# PIC.net
KiCad netlist of a schematic drawn in Altium Designer
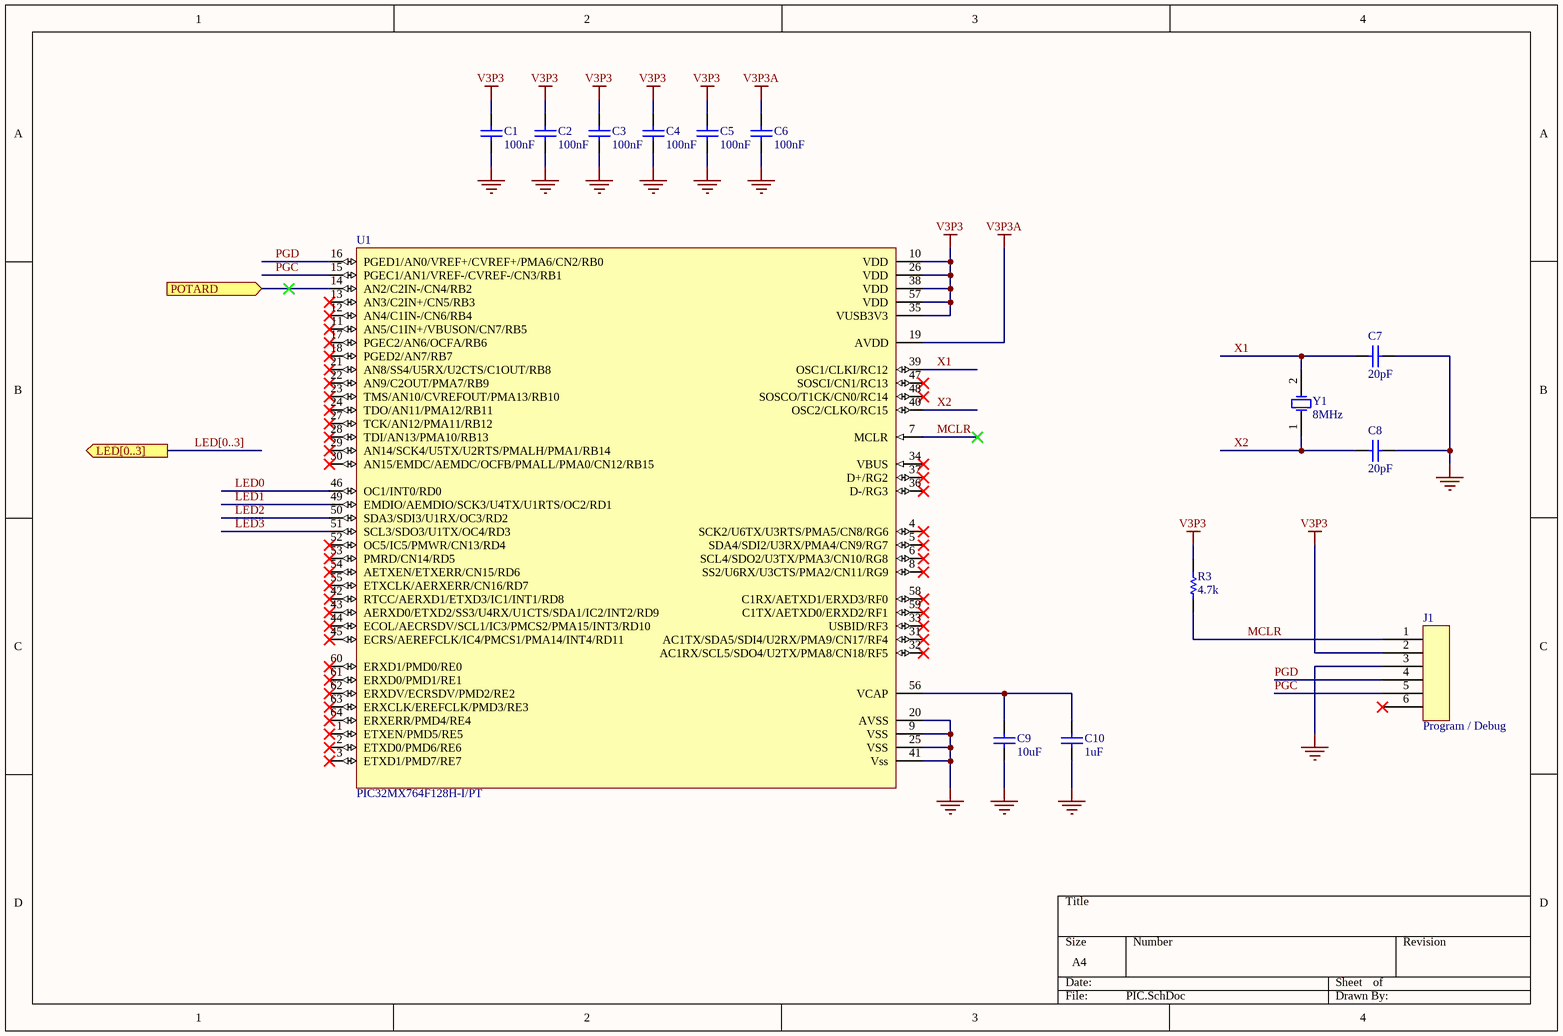
[diagram p0: PIC.SchDoc]

(export (version "E")
  (design (tool "Eeschema 10.0.6"))
  (components
    (comp (ref "C1")
      (value "100nF")
      (footprint "TP2_PcbLib:CAPC1608N")
      (description "Capacitor")
      (fields (field (name "PUBLISHER") "Altium Limited"))
      (libsource (lib "Miscellaneous Devices") (part "Cap"))
    )
    (comp (ref "C2")
      (value "100nF")
      (footprint "TP2_PcbLib:CAPC1608N")
      (description "Capacitor")
      (fields (field (name "PUBLISHER") "Altium Limited"))
      (libsource (lib "Miscellaneous Devices") (part "Cap"))
    )
    (comp (ref "C3")
      (value "100nF")
      (footprint "TP2_PcbLib:CAPC1608N")
      (description "Capacitor")
      (fields (field (name "PUBLISHER") "Altium Limited"))
      (libsource (lib "Miscellaneous Devices") (part "Cap"))
    )
    (comp (ref "C4")
      (value "100nF")
      (footprint "TP2_PcbLib:CAPC1608N")
      (description "Capacitor")
      (fields (field (name "PUBLISHER") "Altium Limited"))
      (libsource (lib "Miscellaneous Devices") (part "Cap"))
    )
    (comp (ref "C5")
      (value "100nF")
      (footprint "TP2_PcbLib:CAPC1608N")
      (description "Capacitor")
      (fields (field (name "PUBLISHER") "Altium Limited"))
      (libsource (lib "Miscellaneous Devices") (part "Cap"))
    )
    (comp (ref "C6")
      (value "100nF")
      (footprint "TP2_PcbLib:CAPC1608N")
      (description "Capacitor")
      (fields (field (name "PUBLISHER") "Altium Limited"))
      (libsource (lib "Miscellaneous Devices") (part "Cap"))
    )
    (comp (ref "C7")
      (value "20pF")
      (footprint "TP2_PcbLib:CAPC1608N")
      (description "Capacitor")
      (fields (field (name "PUBLISHER") "Altium Limited"))
      (libsource (lib "Miscellaneous Devices") (part "Cap"))
    )
    (comp (ref "C8")
      (value "20pF")
      (footprint "TP2_PcbLib:CAPC1608N")
      (description "Capacitor")
      (fields (field (name "PUBLISHER") "Altium Limited"))
      (libsource (lib "Miscellaneous Devices") (part "Cap"))
    )
    (comp (ref "C9")
      (value "10uF")
      (footprint "TP2_PcbLib:CAPC2012N")
      (description "Capacitor")
      (fields (field (name "PUBLISHER") "Altium Limited"))
      (libsource (lib "Miscellaneous Devices") (part "Cap"))
    )
    (comp (ref "C10")
      (value "1uF")
      (footprint "TP2_PcbLib:CAPC1608N")
      (description "Capacitor")
      (fields (field (name "PUBLISHER") "Altium Limited"))
      (libsource (lib "Miscellaneous Devices") (part "Cap"))
    )
    (comp (ref "J1")
      (value "Program / Debug")
      (footprint "TP2_PcbLib:RJ12_90")
      (libsource (lib "Program_Debug") (part "Program / Debug"))
    )
    (comp (ref "R3")
      (value "4.7k")
      (footprint "TP2_PcbLib:RESC1608N")
      (description "Resistor")
      (fields (field (name "PUBLISHER") "Altium Limited"))
      (libsource (lib "Miscellaneous Devices") (part "Res1"))
    )
    (comp (ref "U1")
      (value "PIC32MX764F128H-I/PT")
      (footprint "TP2_PcbLib:QFP50P1200X1200X120-64")
      (libsource (lib "TP2") (part "PIC32MX764F128H-I/PT"))
    )
    (comp (ref "Y1")
      (value "8MHz")
      (footprint "TP2_PcbLib:HC49/4H SMX CRYSTAL")
      (description "Crystal Oscillator")
      (fields (field (name "PUBLISHER") "Altium Limited"))
      (libsource (lib "Miscellaneous Devices") (part "XTAL"))
    )
  )
  (nets
    (net (code "1") (name "/LED0") (class "Default")
      (node (ref "U1") (pin "46") (pinfunction "OC1/INT0/RD0_46") (pintype "bidirectional"))
    )
    (net (code "2") (name "/LED1") (class "Default")
      (node (ref "U1") (pin "49") (pinfunction "EMDIO/AEMDIO/SCK3/U4TX/U1RTS/OC2/RD1_49") (pintype "bidirectional"))
    )
    (net (code "3") (name "/LED2") (class "Default")
      (node (ref "U1") (pin "50") (pinfunction "SDA3/SDI3/U1RX/OC3/RD2_50") (pintype "bidirectional"))
    )
    (net (code "4") (name "/LED3") (class "Default")
      (node (ref "U1") (pin "51") (pinfunction "SCL3/SDO3/U1TX/OC4/RD3_51") (pintype "bidirectional"))
    )
    (net (code "6") (name "/MCLR") (class "Default")
      (node (ref "J1") (pin "1") (pinfunction "*_1") (pintype "passive"))
      (node (ref "R3") (pin "2") (pinfunction "2_2") (pintype "passive"))
      (node (ref "U1") (pin "7") (pinfunction "MCLR_7") (pintype "input"))
    )
    (net (code "7") (name "/PGC") (class "Default")
      (node (ref "J1") (pin "5") (pinfunction "5_5") (pintype "passive"))
      (node (ref "U1") (pin "15") (pinfunction "PGEC1/AN1/VREF-/CVREF-/CN3/RB1_15") (pintype "bidirectional"))
    )
    (net (code "8") (name "/PGD") (class "Default")
      (node (ref "J1") (pin "4") (pinfunction "4_4") (pintype "passive"))
      (node (ref "U1") (pin "16") (pinfunction "PGED1/AN0/VREF+/CVREF+/PMA6/CN2/RB0_16") (pintype "bidirectional"))
    )
    (net (code "9") (name "/POTARD") (class "Default")
      (node (ref "U1") (pin "14") (pinfunction "AN2/C2IN-/CN4/RB2_14") (pintype "bidirectional+no_connect"))
    )
    (net (code "10") (name "/X1") (class "Default")
      (node (ref "C7") (pin "2") (pinfunction "2_2") (pintype "passive"))
      (node (ref "U1") (pin "39") (pinfunction "OSC1/CLKI/RC12_39") (pintype "bidirectional"))
      (node (ref "Y1") (pin "2") (pinfunction "OSC2_2") (pintype "passive"))
    )
    (net (code "11") (name "/X2") (class "Default")
      (node (ref "C8") (pin "2") (pinfunction "2_2") (pintype "passive"))
      (node (ref "U1") (pin "40") (pinfunction "OSC2/CLKO/RC15_40") (pintype "bidirectional"))
      (node (ref "Y1") (pin "1") (pinfunction "OSC1_1") (pintype "passive"))
    )
    (net (code "12") (name "GND") (class "Default")
      (node (ref "C1") (pin "1") (pinfunction "1_1") (pintype "passive"))
      (node (ref "C10") (pin "1") (pinfunction "1_1") (pintype "passive"))
      (node (ref "C2") (pin "1") (pinfunction "1_1") (pintype "passive"))
      (node (ref "C3") (pin "1") (pinfunction "1_1") (pintype "passive"))
      (node (ref "C4") (pin "1") (pinfunction "1_1") (pintype "passive"))
      (node (ref "C5") (pin "1") (pinfunction "1_1") (pintype "passive"))
      (node (ref "C6") (pin "1") (pinfunction "1_1") (pintype "passive"))
      (node (ref "C7") (pin "1") (pinfunction "1_1") (pintype "passive"))
      (node (ref "C8") (pin "1") (pinfunction "1_1") (pintype "passive"))
      (node (ref "C9") (pin "1") (pinfunction "1_1") (pintype "passive"))
      (node (ref "J1") (pin "3") (pinfunction "3_3") (pintype "passive"))
      (node (ref "U1") (pin "20") (pinfunction "AVSS_20") (pintype "passive"))
      (node (ref "U1") (pin "25") (pinfunction "VSS_25") (pintype "passive"))
      (node (ref "U1") (pin "41") (pinfunction "Vss_41") (pintype "passive"))
      (node (ref "U1") (pin "9") (pinfunction "VSS_9") (pintype "passive"))
    )
    (net (code "13") (name "Net-(U1-VCAP)") (class "Default")
      (node (ref "C10") (pin "2") (pinfunction "2_2") (pintype "passive"))
      (node (ref "C9") (pin "2") (pinfunction "2_2") (pintype "passive"))
      (node (ref "U1") (pin "56") (pinfunction "VCAP_56") (pintype "passive"))
    )
    (net (code "14") (name "V3P3") (class "Default")
      (node (ref "C1") (pin "2") (pinfunction "2_2") (pintype "passive"))
      (node (ref "C2") (pin "2") (pinfunction "2_2") (pintype "passive"))
      (node (ref "C3") (pin "2") (pinfunction "2_2") (pintype "passive"))
      (node (ref "C4") (pin "2") (pinfunction "2_2") (pintype "passive"))
      (node (ref "C5") (pin "2") (pinfunction "2_2") (pintype "passive"))
      (node (ref "J1") (pin "2") (pinfunction "2_2") (pintype "passive"))
      (node (ref "R3") (pin "1") (pinfunction "1_1") (pintype "passive"))
      (node (ref "U1") (pin "10") (pinfunction "VDD_10") (pintype "passive"))
      (node (ref "U1") (pin "26") (pinfunction "VDD_26") (pintype "passive"))
      (node (ref "U1") (pin "35") (pinfunction "VUSB3V3_35") (pintype "passive"))
      (node (ref "U1") (pin "38") (pinfunction "VDD_38") (pintype "passive"))
      (node (ref "U1") (pin "57") (pinfunction "VDD_57") (pintype "passive"))
    )
    (net (code "15") (name "V3P3A") (class "Default")
      (node (ref "C6") (pin "2") (pinfunction "2_2") (pintype "passive"))
      (node (ref "U1") (pin "19") (pinfunction "AVDD_19") (pintype "passive"))
    )
    (net (code "16") (name "unconnected-(J1-Pad6)") (class "Default")
      (node (ref "J1") (pin "6") (pinfunction "6_6") (pintype "passive+no_connect"))
    )
    (net (code "17") (name "unconnected-(U1-AC1RX{slash}SCL5{slash}SDO4{slash}U2TX{slash}PMA8{slash}CN18{slash}RF5-Pad32)") (class "Default")
      (node (ref "U1") (pin "32") (pinfunction "AC1RX/SCL5/SDO4/U2TX/PMA8/CN18/RF5_32") (pintype "bidirectional+no_connect"))
    )
    (net (code "18") (name "unconnected-(U1-AC1TX{slash}SDA5{slash}SDI4{slash}U2RX{slash}PMA9{slash}CN17{slash}RF4-Pad31)") (class "Default")
      (node (ref "U1") (pin "31") (pinfunction "AC1TX/SDA5/SDI4/U2RX/PMA9/CN17/RF4_31") (pintype "bidirectional+no_connect"))
    )
    (net (code "19") (name "unconnected-(U1-AERXD0{slash}ETXD2{slash}SS3{slash}U4RX{slash}U1CTS{slash}SDA1{slash}IC2{slash}INT2{slash}RD9-Pad43)") (class "Default")
      (node (ref "U1") (pin "43") (pinfunction "AERXD0/ETXD2/SS3/U4RX/U1CTS/SDA1/IC2/INT2/RD9_43") (pintype "bidirectional+no_connect"))
    )
    (net (code "20") (name "unconnected-(U1-AETXEN{slash}ETXERR{slash}CN15{slash}RD6-Pad54)") (class "Default")
      (node (ref "U1") (pin "54") (pinfunction "AETXEN/ETXERR/CN15/RD6_54") (pintype "bidirectional+no_connect"))
    )
    (net (code "21") (name "unconnected-(U1-AN3{slash}C2IN+{slash}CN5{slash}RB3-Pad13)") (class "Default")
      (node (ref "U1") (pin "13") (pinfunction "AN3/C2IN+/CN5/RB3_13") (pintype "bidirectional+no_connect"))
    )
    (net (code "22") (name "unconnected-(U1-AN4{slash}C1IN-{slash}CN6{slash}RB4-Pad12)") (class "Default")
      (node (ref "U1") (pin "12") (pinfunction "AN4/C1IN-/CN6/RB4_12") (pintype "bidirectional+no_connect"))
    )
    (net (code "23") (name "unconnected-(U1-AN5{slash}C1IN+{slash}VBUSON{slash}CN7{slash}RB5-Pad11)") (class "Default")
      (node (ref "U1") (pin "11") (pinfunction "AN5/C1IN+/VBUSON/CN7/RB5_11") (pintype "bidirectional+no_connect"))
    )
    (net (code "24") (name "unconnected-(U1-AN8{slash}SS4{slash}U5RX{slash}U2CTS{slash}C1OUT{slash}RB8-Pad21)") (class "Default")
      (node (ref "U1") (pin "21") (pinfunction "AN8/SS4/U5RX/U2CTS/C1OUT/RB8_21") (pintype "bidirectional+no_connect"))
    )
    (net (code "25") (name "unconnected-(U1-AN9{slash}C2OUT{slash}PMA7{slash}RB9-Pad22)") (class "Default")
      (node (ref "U1") (pin "22") (pinfunction "AN9/C2OUT/PMA7/RB9_22") (pintype "bidirectional+no_connect"))
    )
    (net (code "26") (name "unconnected-(U1-AN14{slash}SCK4{slash}U5TX{slash}U2RTS{slash}PMALH{slash}PMA1{slash}RB14-Pad29)") (class "Default")
      (node (ref "U1") (pin "29") (pinfunction "AN14/SCK4/U5TX/U2RTS/PMALH/PMA1/RB14_29") (pintype "bidirectional+no_connect"))
    )
    (net (code "27") (name "unconnected-(U1-AN15{slash}EMDC{slash}AEMDC{slash}OCFB{slash}PMALL{slash}PMA0{slash}CN12{slash}RB15-Pad30)") (class "Default")
      (node (ref "U1") (pin "30") (pinfunction "AN15/EMDC/AEMDC/OCFB/PMALL/PMA0/CN12/RB15_30") (pintype "bidirectional+no_connect"))
    )
    (net (code "28") (name "unconnected-(U1-C1RX{slash}AETXD1{slash}ERXD3{slash}RF0-Pad58)") (class "Default")
      (node (ref "U1") (pin "58") (pinfunction "C1RX/AETXD1/ERXD3/RF0_58") (pintype "bidirectional+no_connect"))
    )
    (net (code "29") (name "unconnected-(U1-C1TX{slash}AETXD0{slash}ERXD2{slash}RF1-Pad59)") (class "Default")
      (node (ref "U1") (pin "59") (pinfunction "C1TX/AETXD0/ERXD2/RF1_59") (pintype "bidirectional+no_connect"))
    )
    (net (code "30") (name "unconnected-(U1-D+{slash}RG2-Pad37)") (class "Default")
      (node (ref "U1") (pin "37") (pinfunction "D+/RG2_37") (pintype "bidirectional+no_connect"))
    )
    (net (code "31") (name "unconnected-(U1-D-{slash}RG3-Pad36)") (class "Default")
      (node (ref "U1") (pin "36") (pinfunction "D-/RG3_36") (pintype "bidirectional+no_connect"))
    )
    (net (code "32") (name "unconnected-(U1-ECOL{slash}AECRSDV{slash}SCL1{slash}IC3{slash}PMCS2{slash}PMA15{slash}INT3{slash}RD10-Pad44)") (class "Default")
      (node (ref "U1") (pin "44") (pinfunction "ECOL/AECRSDV/SCL1/IC3/PMCS2/PMA15/INT3/RD10_44") (pintype "bidirectional+no_connect"))
    )
    (net (code "33") (name "unconnected-(U1-ECRS{slash}AEREFCLK{slash}IC4{slash}PMCS1{slash}PMA14{slash}INT4{slash}RD11-Pad45)") (class "Default")
      (node (ref "U1") (pin "45") (pinfunction "ECRS/AEREFCLK/IC4/PMCS1/PMA14/INT4/RD11_45") (pintype "bidirectional+no_connect"))
    )
    (net (code "34") (name "unconnected-(U1-ERXCLK{slash}EREFCLK{slash}PMD3{slash}RE3-Pad63)") (class "Default")
      (node (ref "U1") (pin "63") (pinfunction "ERXCLK/EREFCLK/PMD3/RE3_63") (pintype "bidirectional+no_connect"))
    )
    (net (code "35") (name "unconnected-(U1-ERXD0{slash}PMD1{slash}RE1-Pad61)") (class "Default")
      (node (ref "U1") (pin "61") (pinfunction "ERXD0/PMD1/RE1_61") (pintype "bidirectional+no_connect"))
    )
    (net (code "36") (name "unconnected-(U1-ERXD1{slash}PMD0{slash}RE0-Pad60)") (class "Default")
      (node (ref "U1") (pin "60") (pinfunction "ERXD1/PMD0/RE0_60") (pintype "bidirectional+no_connect"))
    )
    (net (code "37") (name "unconnected-(U1-ERXDV{slash}ECRSDV{slash}PMD2{slash}RE2-Pad62)") (class "Default")
      (node (ref "U1") (pin "62") (pinfunction "ERXDV/ECRSDV/PMD2/RE2_62") (pintype "bidirectional+no_connect"))
    )
    (net (code "38") (name "unconnected-(U1-ERXERR{slash}PMD4{slash}RE4-Pad64)") (class "Default")
      (node (ref "U1") (pin "64") (pinfunction "ERXERR/PMD4/RE4_64") (pintype "bidirectional+no_connect"))
    )
    (net (code "39") (name "unconnected-(U1-ETXCLK{slash}AERXERR{slash}CN16{slash}RD7-Pad55)") (class "Default")
      (node (ref "U1") (pin "55") (pinfunction "ETXCLK/AERXERR/CN16/RD7_55") (pintype "bidirectional+no_connect"))
    )
    (net (code "40") (name "unconnected-(U1-ETXD0{slash}PMD6{slash}RE6-Pad2)") (class "Default")
      (node (ref "U1") (pin "2") (pinfunction "ETXD0/PMD6/RE6_2") (pintype "bidirectional+no_connect"))
    )
    (net (code "41") (name "unconnected-(U1-ETXD1{slash}PMD7{slash}RE7-Pad3)") (class "Default")
      (node (ref "U1") (pin "3") (pinfunction "ETXD1/PMD7/RE7_3") (pintype "bidirectional+no_connect"))
    )
    (net (code "42") (name "unconnected-(U1-ETXEN{slash}PMD5{slash}RE5-Pad1)") (class "Default")
      (node (ref "U1") (pin "1") (pinfunction "ETXEN/PMD5/RE5_1") (pintype "bidirectional+no_connect"))
    )
    (net (code "43") (name "unconnected-(U1-OC5{slash}IC5{slash}PMWR{slash}CN13{slash}RD4-Pad52)") (class "Default")
      (node (ref "U1") (pin "52") (pinfunction "OC5/IC5/PMWR/CN13/RD4_52") (pintype "bidirectional+no_connect"))
    )
    (net (code "44") (name "unconnected-(U1-PGEC2{slash}AN6{slash}OCFA{slash}RB6-Pad17)") (class "Default")
      (node (ref "U1") (pin "17") (pinfunction "PGEC2/AN6/OCFA/RB6_17") (pintype "bidirectional+no_connect"))
    )
    (net (code "45") (name "unconnected-(U1-PGED2{slash}AN7{slash}RB7-Pad18)") (class "Default")
      (node (ref "U1") (pin "18") (pinfunction "PGED2/AN7/RB7_18") (pintype "bidirectional+no_connect"))
    )
    (net (code "46") (name "unconnected-(U1-PMRD{slash}CN14{slash}RD5-Pad53)") (class "Default")
      (node (ref "U1") (pin "53") (pinfunction "PMRD/CN14/RD5_53") (pintype "bidirectional+no_connect"))
    )
    (net (code "47") (name "unconnected-(U1-RTCC{slash}AERXD1{slash}ETXD3{slash}IC1{slash}INT1{slash}RD8-Pad42)") (class "Default")
      (node (ref "U1") (pin "42") (pinfunction "RTCC/AERXD1/ETXD3/IC1/INT1/RD8_42") (pintype "bidirectional+no_connect"))
    )
    (net (code "48") (name "unconnected-(U1-SCK2{slash}U6TX{slash}U3RTS{slash}PMA5{slash}CN8{slash}RG6-Pad4)") (class "Default")
      (node (ref "U1") (pin "4") (pinfunction "SCK2/U6TX/U3RTS/PMA5/CN8/RG6_4") (pintype "bidirectional+no_connect"))
    )
    (net (code "49") (name "unconnected-(U1-SCL4{slash}SDO2{slash}U3TX{slash}PMA3{slash}CN10{slash}RG8-Pad6)") (class "Default")
      (node (ref "U1") (pin "6") (pinfunction "SCL4/SDO2/U3TX/PMA3/CN10/RG8_6") (pintype "bidirectional+no_connect"))
    )
    (net (code "50") (name "unconnected-(U1-SDA4{slash}SDI2{slash}U3RX{slash}PMA4{slash}CN9{slash}RG7-Pad5)") (class "Default")
      (node (ref "U1") (pin "5") (pinfunction "SDA4/SDI2/U3RX/PMA4/CN9/RG7_5") (pintype "bidirectional+no_connect"))
    )
    (net (code "51") (name "unconnected-(U1-SOSCI{slash}CN1{slash}RC13-Pad47)") (class "Default")
      (node (ref "U1") (pin "47") (pinfunction "SOSCI/CN1/RC13_47") (pintype "bidirectional+no_connect"))
    )
    (net (code "52") (name "unconnected-(U1-SOSCO{slash}T1CK{slash}CN0{slash}RC14-Pad48)") (class "Default")
      (node (ref "U1") (pin "48") (pinfunction "SOSCO/T1CK/CN0/RC14_48") (pintype "bidirectional+no_connect"))
    )
    (net (code "53") (name "unconnected-(U1-SS2{slash}U6RX{slash}U3CTS{slash}PMA2{slash}CN11{slash}RG9-Pad8)") (class "Default")
      (node (ref "U1") (pin "8") (pinfunction "SS2/U6RX/U3CTS/PMA2/CN11/RG9_8") (pintype "bidirectional+no_connect"))
    )
    (net (code "54") (name "unconnected-(U1-TCK{slash}AN12{slash}PMA11{slash}RB12-Pad27)") (class "Default")
      (node (ref "U1") (pin "27") (pinfunction "TCK/AN12/PMA11/RB12_27") (pintype "bidirectional+no_connect"))
    )
    (net (code "55") (name "unconnected-(U1-TDI{slash}AN13{slash}PMA10{slash}RB13-Pad28)") (class "Default")
      (node (ref "U1") (pin "28") (pinfunction "TDI/AN13/PMA10/RB13_28") (pintype "bidirectional+no_connect"))
    )
    (net (code "56") (name "unconnected-(U1-TDO{slash}AN11{slash}PMA12{slash}RB11-Pad24)") (class "Default")
      (node (ref "U1") (pin "24") (pinfunction "TDO/AN11/PMA12/RB11_24") (pintype "bidirectional+no_connect"))
    )
    (net (code "57") (name "unconnected-(U1-TMS{slash}AN10{slash}CVREFOUT{slash}PMA13{slash}RB10-Pad23)") (class "Default")
      (node (ref "U1") (pin "23") (pinfunction "TMS/AN10/CVREFOUT/PMA13/RB10_23") (pintype "bidirectional+no_connect"))
    )
    (net (code "58") (name "unconnected-(U1-USBID{slash}RF3-Pad33)") (class "Default")
      (node (ref "U1") (pin "33") (pinfunction "USBID/RF3_33") (pintype "bidirectional+no_connect"))
    )
    (net (code "59") (name "unconnected-(U1-VBUS-Pad34)") (class "Default")
      (node (ref "U1") (pin "34") (pinfunction "VBUS_34") (pintype "input+no_connect"))
    )
  )
)
